# HDC2080_breakout_sch.net
KiCad netlist of a schematic drawn in EAGLE
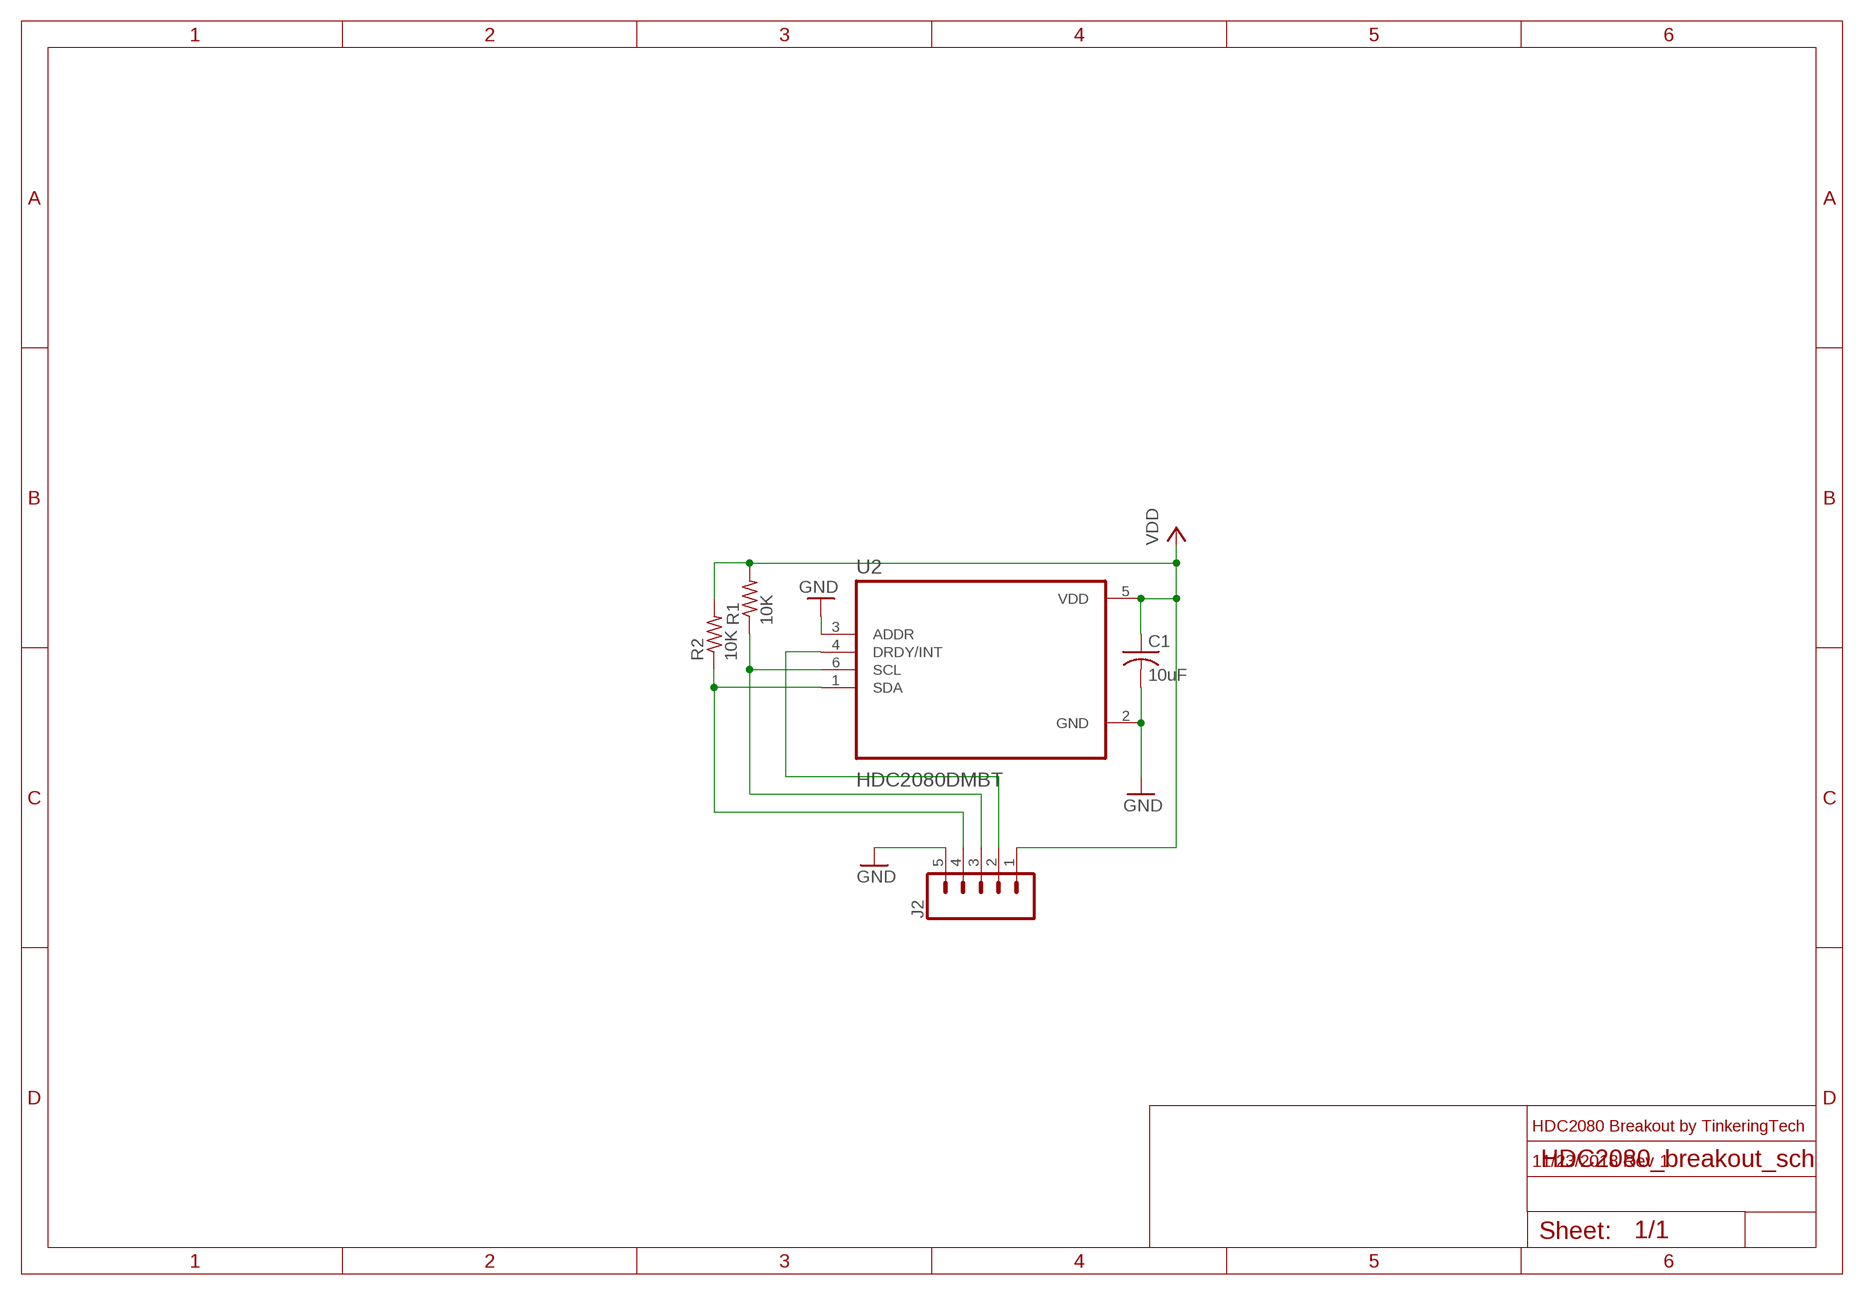
[diagram p0: schematic, sheet 1]

(export (version "E")
  (design (tool "Eeschema 10.0.6"))
  (components
    (comp (ref "C1")
      (value "10uF")
      (footprint "eagle-import:C0402")
      (libsource (lib "eagle-import") (part "C-USC0402"))
    )
    (comp (ref "J2")
      (value "CONN_05")
      (footprint "eagle-import:1X05")
      (libsource (lib "eagle-import") (part "CONN_05"))
    )
    (comp (ref "R1")
      (value "10K")
      (footprint "eagle-import:R0402")
      (libsource (lib "eagle-import") (part "R-US_R0402"))
    )
    (comp (ref "R2")
      (value "10K")
      (footprint "eagle-import:R0402")
      (libsource (lib "eagle-import") (part "R-US_R0402"))
    )
    (comp (ref "U2")
      (value "HDC2080DMBT")
      (footprint "eagle-import:SON100P300X300X80-7N")
      (fields (field (name "MF") "Texas Instruments"))
      (libsource (lib "eagle-import") (part "HDC2080DMBT"))
    )
  )
  (nets
    (net (code "1") (name "GND") (class "Default")
      (node (ref "C1") (pin "2") (pinfunction "2_2") (pintype "passive"))
      (node (ref "J2") (pin "5") (pinfunction "5_5") (pintype "passive"))
      (node (ref "U2") (pin "2") (pinfunction "GND_2") (pintype "power_in"))
      (node (ref "U2") (pin "3") (pinfunction "ADDR_3") (pintype "bidirectional"))
    )
    (net (code "2") (name "Net-(U2-DRDY{slash}INT)") (class "Default")
      (node (ref "J2") (pin "2") (pinfunction "2_2") (pintype "passive"))
      (node (ref "U2") (pin "4") (pinfunction "DRDY/INT_4") (pintype "bidirectional"))
    )
    (net (code "3") (name "Net-(U2-SCL)") (class "Default")
      (node (ref "J2") (pin "3") (pinfunction "3_3") (pintype "passive"))
      (node (ref "R1") (pin "1") (pinfunction "1_1") (pintype "passive"))
      (node (ref "U2") (pin "6") (pinfunction "SCL_6") (pintype "bidirectional"))
    )
    (net (code "4") (name "Net-(U2-SDA)") (class "Default")
      (node (ref "J2") (pin "4") (pinfunction "4_4") (pintype "passive"))
      (node (ref "R2") (pin "1") (pinfunction "1_1") (pintype "passive"))
      (node (ref "U2") (pin "1") (pinfunction "SDA_1") (pintype "bidirectional"))
    )
    (net (code "5") (name "VDD") (class "Default")
      (node (ref "C1") (pin "1") (pinfunction "1_1") (pintype "passive"))
      (node (ref "J2") (pin "1") (pinfunction "1_1") (pintype "passive"))
      (node (ref "R1") (pin "2") (pinfunction "2_2") (pintype "passive"))
      (node (ref "R2") (pin "2") (pinfunction "2_2") (pintype "passive"))
      (node (ref "U2") (pin "5") (pinfunction "VDD_5") (pintype "power_in"))
    )
  )
)
